# MCU.net
KiCad netlist of a schematic drawn in Altium Designer
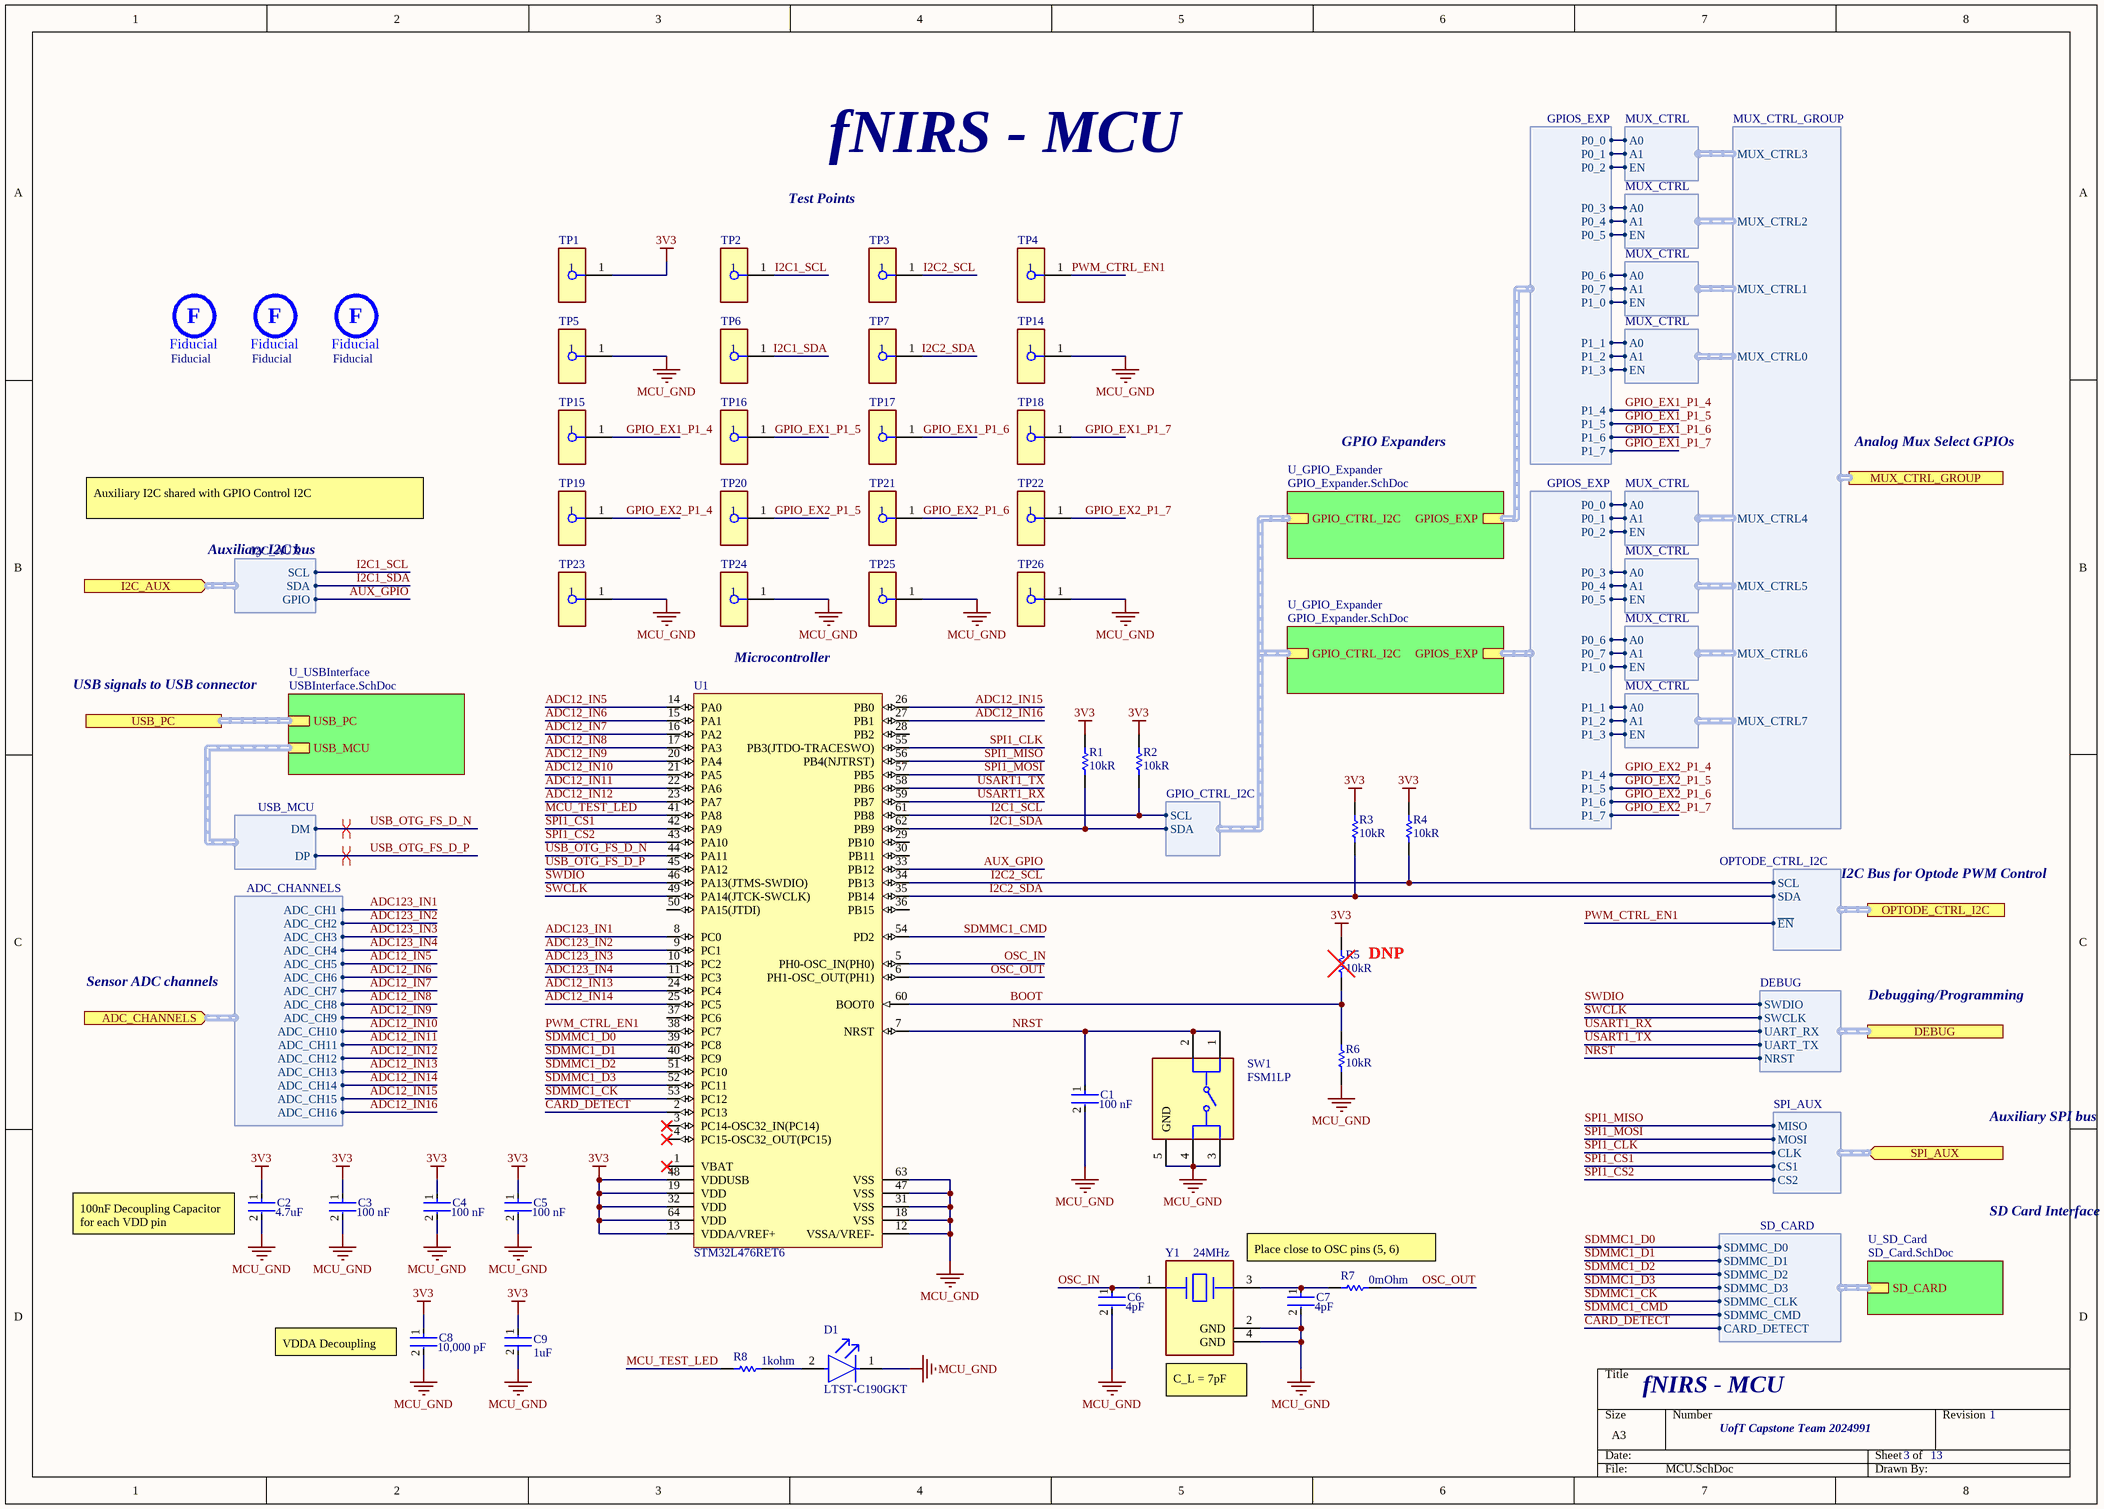
[diagram p0: MCU.SchDoc]

(export (version "E")
  (design (tool "Eeschema 10.0.6"))
  (components
    (comp (ref "C1")
      (value "CC0603KRX7R7BB104")
      (footprint "FP-CC0603-DA-MFG")
      (description "CAP CER 0.1UF 16V X7R 0603")
      (fields
        (field (name "OCTOPART") "https://octopart.com/cc0603krx7r7bb104-yageo-192941")
        (field (name "TOLERANCE") "0.1")
        (field (name "CAPACITANCE") "100 nF")
      )
      (libsource (lib "Altium Content Vault") (part "11868f565c42a9108669ba33697ecf6"))
    )
    (comp (ref "C2")
      (value "C0603C475K9PACTU")
      (footprint "FP-C0603-CG-MFG")
      (description "CAP CER 4.7UF 6.3V X5R 0603")
      (fields
        (field (name "TOLERANCE") "10%")
        (field (name "MANUFACTURER") "Kemet")
        (field (name "CAPACITANCE") "4.7uF")
      )
      (libsource (lib "Altium Content Vault") (part "11868f565c42a9108669ba33697ecf6"))
    )
    (comp (ref "C3")
      (value "CC0603KRX7R7BB104")
      (footprint "FP-CC0603-DA-MFG")
      (description "CAP CER 0.1UF 16V X7R 0603")
      (fields
        (field (name "OCTOPART") "https://octopart.com/cc0603krx7r7bb104-yageo-192941")
        (field (name "TOLERANCE") "0.1")
        (field (name "CAPACITANCE") "100 nF")
      )
      (libsource (lib "Altium Content Vault") (part "11868f565c42a9108669ba33697ecf6"))
    )
    (comp (ref "C4")
      (value "CC0603KRX7R7BB104")
      (footprint "FP-CC0603-DA-MFG")
      (description "CAP CER 0.1UF 16V X7R 0603")
      (fields
        (field (name "OCTOPART") "https://octopart.com/cc0603krx7r7bb104-yageo-192941")
        (field (name "TOLERANCE") "0.1")
        (field (name "CAPACITANCE") "100 nF")
      )
      (libsource (lib "Altium Content Vault") (part "11868f565c42a9108669ba33697ecf6"))
    )
    (comp (ref "C5")
      (value "CC0603KRX7R7BB104")
      (footprint "FP-CC0603-DA-MFG")
      (description "CAP CER 0.1UF 16V X7R 0603")
      (fields
        (field (name "OCTOPART") "https://octopart.com/cc0603krx7r7bb104-yageo-192941")
        (field (name "TOLERANCE") "0.1")
        (field (name "CAPACITANCE") "100 nF")
      )
      (libsource (lib "Altium Content Vault") (part "11868f565c42a9108669ba33697ecf6"))
    )
    (comp (ref "C6")
      (value "CL10C040CB8NNNC")
      (footprint "FP-CL10-IPC_A")
      (description "Cap Ceramic 4pF 50V C0G ±0.25pF Pad SMD 0603 +125°C T/R")
      (fields (field (name "CAPACITANCE") "4pF") (field (name "TOLERANCE") "-0.25%"))
      (libsource (lib "Altium Content Vault") (part "b4654b650e69147ec39a6b967a45e02"))
    )
    (comp (ref "C7")
      (value "CL10C040CB8NNNC")
      (footprint "FP-CL10-IPC_A")
      (description "Cap Ceramic 4pF 50V C0G ±0.25pF Pad SMD 0603 +125°C T/R")
      (fields (field (name "CAPACITANCE") "4pF") (field (name "TOLERANCE") "-0.25%"))
      (libsource (lib "Altium Content Vault") (part "b4654b650e69147ec39a6b967a45e02"))
    )
    (comp (ref "C8")
      (value "C0603C103K2RACTU")
      (footprint "FP-C0603C-CF-MFG")
      (description "CAP CER 10000PF 200V X7R 0603")
      (fields
        (field (name "MANUFACTURER") "KEMET")
        (field (name "OCTOPART") "https://octopart.com/c0603c103k2ractu-kemet-1061947")
        (field (name "CAPACITANCE") "10,000 pF")
      )
      (libsource (lib "Altium Content Vault") (part "b4654b650e69147ec39a6b967a45e02"))
    )
    (comp (ref "C9")
      (value "C1608X5R1H105K080AB")
      (footprint "FP-C1608-080-0_1-IPC_B")
      (description "Multilayer Ceramic Capacitors 1μF ±10% 50V X5R SMD 0603")
      (fields
        (field (name "VOLTAGE") "50V")
        (field (name "CAPACITANCE") "1uF")
        (field (name "TOLERANCE") "10%")
      )
      (libsource (lib "Altium Content Vault") (part "236180d848d6139a670b325ea6854c9"))
    )
    (comp (ref "D1")
      (value "LTST-C190GKT")
      (footprint "FP-LTST-C190GKT-MFG")
      (description "LED GREEN CLEAR CHIP SMD")
      (fields (field (name "VOLTAGE") "2V"))
      (libsource (lib "Altium Content Vault") (part "8706943c75ba83719d021d2fdc84c58"))
    )
    (comp (ref "Fi1")
      (value "Fiducial")
      (footprint "Fiducial-Footprint-1")
      (description "Fiducial for pick-and-place")
      (libsource (lib "Blue Sky Solar Racing") (part "Fiducial"))
    )
    (comp (ref "Fi2")
      (value "Fiducial")
      (footprint "Fiducial-Footprint-1")
      (description "Fiducial for pick-and-place")
      (libsource (lib "Blue Sky Solar Racing") (part "Fiducial"))
    )
    (comp (ref "Fi3")
      (value "Fiducial")
      (footprint "Fiducial-Footprint-1")
      (description "Fiducial for pick-and-place")
      (libsource (lib "Blue Sky Solar Racing") (part "Fiducial"))
    )
    (comp (ref "R1")
      (value "CRCW060310K0FKEA")
      (footprint "RESC1609X50X30NL8T20")
      (description "Chip Resistor, 10 KOhm, +/- 1%, 100 mW, -55 to 155 degC, 0603 (1608 Metric), RoHS, Tape and Reel")
      (fields (field (name "MANUFACTURER") "Vishay Semiconductor") (field (name "RESISTANCE") "10kR"))
      (libsource (lib "Altium Content Vault") (part "RES-2"))
    )
    (comp (ref "R2")
      (value "CRCW060310K0FKEA")
      (footprint "RESC1609X50X30NL8T20")
      (description "Chip Resistor, 10 KOhm, +/- 1%, 100 mW, -55 to 155 degC, 0603 (1608 Metric), RoHS, Tape and Reel")
      (fields (field (name "MANUFACTURER") "Vishay Semiconductor") (field (name "RESISTANCE") "10kR"))
      (libsource (lib "Altium Content Vault") (part "RES-2"))
    )
    (comp (ref "R3")
      (value "CRCW060310K0FKEA")
      (footprint "RESC1609X50X30NL8T20")
      (description "Chip Resistor, 10 KOhm, +/- 1%, 100 mW, -55 to 155 degC, 0603 (1608 Metric), RoHS, Tape and Reel")
      (fields (field (name "MANUFACTURER") "Vishay Semiconductor") (field (name "RESISTANCE") "10kR"))
      (libsource (lib "Altium Content Vault") (part "RES-2"))
    )
    (comp (ref "R4")
      (value "CRCW060310K0FKEA")
      (footprint "RESC1609X50X30NL8T20")
      (description "Chip Resistor, 10 KOhm, +/- 1%, 100 mW, -55 to 155 degC, 0603 (1608 Metric), RoHS, Tape and Reel")
      (fields (field (name "MANUFACTURER") "Vishay Semiconductor") (field (name "RESISTANCE") "10kR"))
      (libsource (lib "Altium Content Vault") (part "RES-2"))
    )
    (comp (ref "R5")
      (value "CRCW060310K0FKEA")
      (footprint "RESC1609X50X30NL8T20")
      (description "Chip Resistor, 10 KOhm, +/- 1%, 100 mW, -55 to 155 degC, 0603 (1608 Metric), RoHS, Tape and Reel")
      (fields (field (name "MANUFACTURER") "Vishay Semiconductor") (field (name "RESISTANCE") "10kR"))
      (libsource (lib "Altium Content Vault") (part "RES-2"))
    )
    (comp (ref "R6")
      (value "CRCW060310K0FKEA")
      (footprint "RESC1609X50X30NL8T20")
      (description "Chip Resistor, 10 KOhm, +/- 1%, 100 mW, -55 to 155 degC, 0603 (1608 Metric), RoHS, Tape and Reel")
      (fields (field (name "MANUFACTURER") "Vishay Semiconductor") (field (name "RESISTANCE") "10kR"))
      (libsource (lib "Altium Content Vault") (part "RES-2"))
    )
    (comp (ref "R7")
      (value "RC0603JR-070RL")
      (footprint "RESC1608X55X25ML10T15")
      (description "Chip Resistor, 0 Ohm, +/- 5%, 0.1 W, -55 to 155 degC, 0603 (1608 Metric), RoHS, Tape and Reel")
      (fields
        (field (name "TOLERANCE") "5%")
        (field (name "RESISTANCE") "0mOhm")
        (field (name "MANUFACTURER") "Yageo")
      )
      (libsource (lib "Altium Content Vault") (part "RES-2"))
    )
    (comp (ref "R8")
      (value "RC0603JR-071KL")
      (footprint "RESC1608X55X25ML10T15")
      (description "Chip Resistor, 1 KOhm, +/- 5%, 0.063 W, -55 to 155 degC, 0603 (1608 Metric), RoHS, Tape and Reel")
      (fields (field (name "RESISTANCE") "1kohm") (field (name "MANUFACTURER") "Yageo"))
      (libsource (lib "Altium Content Vault") (part "RES-2"))
    )
    (comp (ref "SW1")
      (value "FSM1LP")
      (footprint "FP-FSM1LP-MFG")
      (description "SWITCH TACTILE SPST-NO 0.05A 24V")
      (libsource (lib "Altium Content Vault") (part "3a9e64be5c1b186b34f28721102267a"))
    )
    (comp (ref "TP1")
      (value "S2761-46R")
      (footprint "FP-S2761-46R-MFG")
      (description "PC TEST POINT NATURAL")
      (libsource (lib "Altium Content Vault") (part "98815daf2f2c152b0c43f5ab9800df6"))
    )
    (comp (ref "TP2")
      (value "S2761-46R")
      (footprint "FP-S2761-46R-MFG")
      (description "PC TEST POINT NATURAL")
      (libsource (lib "Altium Content Vault") (part "98815daf2f2c152b0c43f5ab9800df6"))
    )
    (comp (ref "TP3")
      (value "S2761-46R")
      (footprint "FP-S2761-46R-MFG")
      (description "PC TEST POINT NATURAL")
      (libsource (lib "Altium Content Vault") (part "98815daf2f2c152b0c43f5ab9800df6"))
    )
    (comp (ref "TP4")
      (value "S2761-46R")
      (footprint "FP-S2761-46R-MFG")
      (description "PC TEST POINT NATURAL")
      (libsource (lib "Altium Content Vault") (part "98815daf2f2c152b0c43f5ab9800df6"))
    )
    (comp (ref "TP5")
      (value "S2761-46R")
      (footprint "FP-S2761-46R-MFG")
      (description "PC TEST POINT NATURAL")
      (libsource (lib "Altium Content Vault") (part "98815daf2f2c152b0c43f5ab9800df6"))
    )
    (comp (ref "TP6")
      (value "S2761-46R")
      (footprint "FP-S2761-46R-MFG")
      (description "PC TEST POINT NATURAL")
      (libsource (lib "Altium Content Vault") (part "98815daf2f2c152b0c43f5ab9800df6"))
    )
    (comp (ref "TP7")
      (value "S2761-46R")
      (footprint "FP-S2761-46R-MFG")
      (description "PC TEST POINT NATURAL")
      (libsource (lib "Altium Content Vault") (part "98815daf2f2c152b0c43f5ab9800df6"))
    )
    (comp (ref "TP14")
      (value "S2761-46R")
      (footprint "FP-S2761-46R-MFG")
      (description "PC TEST POINT NATURAL")
      (libsource (lib "Altium Content Vault") (part "98815daf2f2c152b0c43f5ab9800df6"))
    )
    (comp (ref "TP15")
      (value "S2761-46R")
      (footprint "FP-S2761-46R-MFG")
      (description "PC TEST POINT NATURAL")
      (libsource (lib "Altium Content Vault") (part "98815daf2f2c152b0c43f5ab9800df6"))
    )
    (comp (ref "TP16")
      (value "S2761-46R")
      (footprint "FP-S2761-46R-MFG")
      (description "PC TEST POINT NATURAL")
      (libsource (lib "Altium Content Vault") (part "98815daf2f2c152b0c43f5ab9800df6"))
    )
    (comp (ref "TP17")
      (value "S2761-46R")
      (footprint "FP-S2761-46R-MFG")
      (description "PC TEST POINT NATURAL")
      (libsource (lib "Altium Content Vault") (part "98815daf2f2c152b0c43f5ab9800df6"))
    )
    (comp (ref "TP18")
      (value "S2761-46R")
      (footprint "FP-S2761-46R-MFG")
      (description "PC TEST POINT NATURAL")
      (libsource (lib "Altium Content Vault") (part "98815daf2f2c152b0c43f5ab9800df6"))
    )
    (comp (ref "TP19")
      (value "S2761-46R")
      (footprint "FP-S2761-46R-MFG")
      (description "PC TEST POINT NATURAL")
      (libsource (lib "Altium Content Vault") (part "98815daf2f2c152b0c43f5ab9800df6"))
    )
    (comp (ref "TP20")
      (value "S2761-46R")
      (footprint "FP-S2761-46R-MFG")
      (description "PC TEST POINT NATURAL")
      (libsource (lib "Altium Content Vault") (part "98815daf2f2c152b0c43f5ab9800df6"))
    )
    (comp (ref "TP21")
      (value "S2761-46R")
      (footprint "FP-S2761-46R-MFG")
      (description "PC TEST POINT NATURAL")
      (libsource (lib "Altium Content Vault") (part "98815daf2f2c152b0c43f5ab9800df6"))
    )
    (comp (ref "TP22")
      (value "S2761-46R")
      (footprint "FP-S2761-46R-MFG")
      (description "PC TEST POINT NATURAL")
      (libsource (lib "Altium Content Vault") (part "98815daf2f2c152b0c43f5ab9800df6"))
    )
    (comp (ref "TP23")
      (value "S2761-46R")
      (footprint "FP-S2761-46R-MFG")
      (description "PC TEST POINT NATURAL")
      (libsource (lib "Altium Content Vault") (part "98815daf2f2c152b0c43f5ab9800df6"))
    )
    (comp (ref "TP24")
      (value "S2761-46R")
      (footprint "FP-S2761-46R-MFG")
      (description "PC TEST POINT NATURAL")
      (libsource (lib "Altium Content Vault") (part "98815daf2f2c152b0c43f5ab9800df6"))
    )
    (comp (ref "TP25")
      (value "S2761-46R")
      (footprint "FP-S2761-46R-MFG")
      (description "PC TEST POINT NATURAL")
      (libsource (lib "Altium Content Vault") (part "98815daf2f2c152b0c43f5ab9800df6"))
    )
    (comp (ref "TP26")
      (value "S2761-46R")
      (footprint "FP-S2761-46R-MFG")
      (description "PC TEST POINT NATURAL")
      (libsource (lib "Altium Content Vault") (part "98815daf2f2c152b0c43f5ab9800df6"))
    )
    (comp (ref "U1")
      (value "STM32L476RET6")
      (footprint "STM-LQFP64_L")
      (fields (field (name "MANUFACTURER") "STMicroelectronics"))
      (libsource (lib "Altium Content Vault") (part "MC-ARM-STM32L4X6-LQFP64"))
    )
    (comp (ref "Y1")
      (value "ABM11W-24.0000MHZ-7-B1U-T3")
      (footprint "FP-ABM11W-MFG")
      (description "Crystal 24MHz ±10ppm 7pF SMD-4 2mm x 1.6mm")
      (fields (field (name "FREQUENCY") "24MHz"))
      (libsource (lib "Altium Content Vault") (part "5fba445d8d5f95165d6b3865099b029"))
    )
  )
  (nets
    (net (code "13") (name "/ADC12_IN5") (class "Default")
      (node (ref "U1") (pin "14") (pinfunction "PA0_14") (pintype "bidirectional"))
    )
    (net (code "14") (name "/ADC12_IN6") (class "Default")
      (node (ref "U1") (pin "15") (pinfunction "PA1_15") (pintype "bidirectional"))
    )
    (net (code "15") (name "/ADC12_IN7") (class "Default")
      (node (ref "U1") (pin "16") (pinfunction "PA2_16") (pintype "bidirectional"))
    )
    (net (code "16") (name "/ADC12_IN8") (class "Default")
      (node (ref "U1") (pin "17") (pinfunction "PA3_17") (pintype "bidirectional"))
    )
    (net (code "17") (name "/ADC12_IN9") (class "Default")
      (node (ref "U1") (pin "20") (pinfunction "PA4_20") (pintype "bidirectional"))
    )
    (net (code "18") (name "/ADC12_IN10") (class "Default")
      (node (ref "U1") (pin "21") (pinfunction "PA5_21") (pintype "bidirectional"))
    )
    (net (code "19") (name "/ADC12_IN11") (class "Default")
      (node (ref "U1") (pin "22") (pinfunction "PA6_22") (pintype "bidirectional"))
    )
    (net (code "20") (name "/ADC12_IN12") (class "Default")
      (node (ref "U1") (pin "23") (pinfunction "PA7_23") (pintype "bidirectional"))
    )
    (net (code "21") (name "/ADC12_IN13") (class "Default")
      (node (ref "U1") (pin "24") (pinfunction "PC4_24") (pintype "bidirectional"))
    )
    (net (code "22") (name "/ADC12_IN14") (class "Default")
      (node (ref "U1") (pin "25") (pinfunction "PC5_25") (pintype "bidirectional"))
    )
    (net (code "23") (name "/ADC12_IN15") (class "Default")
      (node (ref "U1") (pin "26") (pinfunction "PB0_26") (pintype "bidirectional"))
    )
    (net (code "24") (name "/ADC12_IN16") (class "Default")
      (node (ref "U1") (pin "27") (pinfunction "PB1_27") (pintype "bidirectional"))
    )
    (net (code "25") (name "/ADC123_IN1") (class "Default")
      (node (ref "U1") (pin "8") (pinfunction "PC0_8") (pintype "bidirectional"))
    )
    (net (code "26") (name "/ADC123_IN2") (class "Default")
      (node (ref "U1") (pin "9") (pinfunction "PC1_9") (pintype "bidirectional"))
    )
    (net (code "27") (name "/ADC123_IN3") (class "Default")
      (node (ref "U1") (pin "10") (pinfunction "PC2_10") (pintype "bidirectional"))
    )
    (net (code "28") (name "/ADC123_IN4") (class "Default")
      (node (ref "U1") (pin "11") (pinfunction "PC3_11") (pintype "bidirectional"))
    )
    (net (code "29") (name "/AUX_GPIO") (class "Default")
      (node (ref "U1") (pin "33") (pinfunction "PB12_33") (pintype "bidirectional"))
    )
    (net (code "30") (name "/BOOT") (class "Default")
      (node (ref "R5") (pin "1") (pinfunction "1_1") (pintype "passive"))
      (node (ref "R6") (pin "2") (pinfunction "2_2") (pintype "passive"))
      (node (ref "U1") (pin "60") (pinfunction "BOOT0_60") (pintype "input"))
    )
    (net (code "31") (name "/CARD_DETECT") (class "Default")
      (node (ref "U1") (pin "2") (pinfunction "PC13_2") (pintype "bidirectional"))
    )
    (net (code "32") (name "/GPIO_EX1_P1_4") (class "Default")
      (node (ref "TP15") (pin "1") (pinfunction "1_1") (pintype "passive"))
    )
    (net (code "33") (name "/GPIO_EX1_P1_5") (class "Default")
      (node (ref "TP16") (pin "1") (pinfunction "1_1") (pintype "passive"))
    )
    (net (code "34") (name "/GPIO_EX1_P1_6") (class "Default")
      (node (ref "TP17") (pin "1") (pinfunction "1_1") (pintype "passive"))
    )
    (net (code "35") (name "/GPIO_EX1_P1_7") (class "Default")
      (node (ref "TP18") (pin "1") (pinfunction "1_1") (pintype "passive"))
    )
    (net (code "36") (name "/GPIO_EX2_P1_4") (class "Default")
      (node (ref "TP19") (pin "1") (pinfunction "1_1") (pintype "passive"))
    )
    (net (code "37") (name "/GPIO_EX2_P1_5") (class "Default")
      (node (ref "TP20") (pin "1") (pinfunction "1_1") (pintype "passive"))
    )
    (net (code "38") (name "/GPIO_EX2_P1_6") (class "Default")
      (node (ref "TP21") (pin "1") (pinfunction "1_1") (pintype "passive"))
    )
    (net (code "39") (name "/GPIO_EX2_P1_7") (class "Default")
      (node (ref "TP22") (pin "1") (pinfunction "1_1") (pintype "passive"))
    )
    (net (code "40") (name "/I2C1_SCL") (class "Default")
      (node (ref "R2") (pin "1") (pinfunction "1_1") (pintype "passive"))
      (node (ref "TP2") (pin "1") (pinfunction "1_1") (pintype "passive"))
      (node (ref "U1") (pin "61") (pinfunction "PB8_61") (pintype "bidirectional"))
    )
    (net (code "41") (name "/I2C1_SDA") (class "Default")
      (node (ref "R1") (pin "1") (pinfunction "1_1") (pintype "passive"))
      (node (ref "TP6") (pin "1") (pinfunction "1_1") (pintype "passive"))
      (node (ref "U1") (pin "62") (pinfunction "PB9_62") (pintype "bidirectional"))
    )
    (net (code "42") (name "/I2C2_SCL") (class "Default")
      (node (ref "R4") (pin "1") (pinfunction "1_1") (pintype "passive"))
      (node (ref "TP3") (pin "1") (pinfunction "1_1") (pintype "passive"))
      (node (ref "U1") (pin "34") (pinfunction "PB13_34") (pintype "bidirectional"))
    )
    (net (code "43") (name "/I2C2_SDA") (class "Default")
      (node (ref "R3") (pin "1") (pinfunction "1_1") (pintype "passive"))
      (node (ref "TP7") (pin "1") (pinfunction "1_1") (pintype "passive"))
      (node (ref "U1") (pin "35") (pinfunction "PB14_35") (pintype "bidirectional"))
    )
    (net (code "44") (name "/MCU_TEST_LED") (class "Default")
      (node (ref "R8") (pin "1") (pinfunction "1_1") (pintype "passive"))
      (node (ref "U1") (pin "41") (pinfunction "PA8_41") (pintype "bidirectional"))
    )
    (net (code "46") (name "/NRST") (class "Default")
      (node (ref "C1") (pin "1") (pinfunction "1_1") (pintype "passive"))
      (node (ref "SW1") (pin "1") (pinfunction "1_1") (pintype "passive"))
      (node (ref "SW1") (pin "2") (pinfunction "2_2") (pintype "passive"))
      (node (ref "U1") (pin "7") (pinfunction "NRST_7") (pintype "bidirectional"))
    )
    (net (code "47") (name "/OSC_IN") (class "Default")
      (node (ref "C6") (pin "1") (pinfunction "1_1") (pintype "passive"))
      (node (ref "U1") (pin "5") (pinfunction "PH0-OSC_IN(PH0)_5") (pintype "bidirectional"))
      (node (ref "Y1") (pin "1") (pinfunction "1_1") (pintype "passive"))
    )
    (net (code "48") (name "/OSC_OUT") (class "Default")
      (node (ref "R7") (pin "2") (pinfunction "2_2") (pintype "passive"))
      (node (ref "U1") (pin "6") (pinfunction "PH1-OSC_OUT(PH1)_6") (pintype "bidirectional"))
    )
    (net (code "49") (name "/PWM_CTRL_EN1") (class "Default")
      (node (ref "TP4") (pin "1") (pinfunction "1_1") (pintype "passive"))
      (node (ref "U1") (pin "38") (pinfunction "PC7_38") (pintype "bidirectional"))
    )
    (net (code "50") (name "/SDMMC1_CK") (class "Default")
      (node (ref "U1") (pin "53") (pinfunction "PC12_53") (pintype "bidirectional"))
    )
    (net (code "51") (name "/SDMMC1_CMD") (class "Default")
      (node (ref "U1") (pin "54") (pinfunction "PD2_54") (pintype "bidirectional"))
    )
    (net (code "52") (name "/SDMMC1_D0") (class "Default")
      (node (ref "U1") (pin "39") (pinfunction "PC8_39") (pintype "bidirectional"))
    )
    (net (code "53") (name "/SDMMC1_D1") (class "Default")
      (node (ref "U1") (pin "40") (pinfunction "PC9_40") (pintype "bidirectional"))
    )
    (net (code "54") (name "/SDMMC1_D2") (class "Default")
      (node (ref "U1") (pin "51") (pinfunction "PC10_51") (pintype "bidirectional"))
    )
    (net (code "55") (name "/SDMMC1_D3") (class "Default")
      (node (ref "U1") (pin "52") (pinfunction "PC11_52") (pintype "bidirectional"))
    )
    (net (code "56") (name "/SPI1_CLK") (class "Default")
      (node (ref "U1") (pin "55") (pinfunction "PB3(JTDO-TRACESWO)_55") (pintype "bidirectional"))
    )
    (net (code "57") (name "/SPI1_CS1") (class "Default")
      (node (ref "U1") (pin "42") (pinfunction "PA9_42") (pintype "bidirectional"))
    )
    (net (code "58") (name "/SPI1_CS2") (class "Default")
      (node (ref "U1") (pin "43") (pinfunction "PA10_43") (pintype "bidirectional"))
    )
    (net (code "59") (name "/SPI1_MISO") (class "Default")
      (node (ref "U1") (pin "56") (pinfunction "PB4(NJTRST)_56") (pintype "bidirectional"))
    )
    (net (code "60") (name "/SPI1_MOSI") (class "Default")
      (node (ref "U1") (pin "57") (pinfunction "PB5_57") (pintype "bidirectional"))
    )
    (net (code "61") (name "/SWCLK") (class "Default")
      (node (ref "U1") (pin "49") (pinfunction "PA14(JTCK-SWCLK)_49") (pintype "bidirectional"))
    )
    (net (code "62") (name "/SWDIO") (class "Default")
      (node (ref "U1") (pin "46") (pinfunction "PA13(JTMS-SWDIO)_46") (pintype "bidirectional"))
    )
    (net (code "63") (name "/USART1_RX") (class "Default")
      (node (ref "U1") (pin "59") (pinfunction "PB7_59") (pintype "bidirectional"))
    )
    (net (code "64") (name "/USART1_TX") (class "Default")
      (node (ref "U1") (pin "58") (pinfunction "PB6_58") (pintype "bidirectional"))
    )
    (net (code "65") (name "/USB_OTG_FS_D_N") (class "Default")
      (node (ref "U1") (pin "44") (pinfunction "PA11_44") (pintype "bidirectional"))
    )
    (net (code "66") (name "/USB_OTG_FS_D_P") (class "Default")
      (node (ref "U1") (pin "45") (pinfunction "PA12_45") (pintype "bidirectional"))
    )
    (net (code "78") (name "3V3") (class "Default")
      (node (ref "C2") (pin "1") (pinfunction "1_1") (pintype "passive"))
      (node (ref "C3") (pin "1") (pinfunction "1_1") (pintype "passive"))
      (node (ref "C4") (pin "1") (pinfunction "1_1") (pintype "passive"))
      (node (ref "C5") (pin "1") (pinfunction "1_1") (pintype "passive"))
      (node (ref "C8") (pin "1") (pinfunction "1_1") (pintype "passive"))
      (node (ref "C9") (pin "1") (pinfunction "1_1") (pintype "passive"))
      (node (ref "R1") (pin "2") (pinfunction "2_2") (pintype "passive"))
      (node (ref "R2") (pin "2") (pinfunction "2_2") (pintype "passive"))
      (node (ref "R3") (pin "2") (pinfunction "2_2") (pintype "passive"))
      (node (ref "R4") (pin "2") (pinfunction "2_2") (pintype "passive"))
      (node (ref "R5") (pin "2") (pinfunction "2_2") (pintype "passive"))
      (node (ref "TP1") (pin "1") (pinfunction "1_1") (pintype "passive"))
      (node (ref "U1") (pin "13") (pinfunction "VDDA/VREF+_13") (pintype "power_in"))
      (node (ref "U1") (pin "19") (pinfunction "VDD_19") (pintype "power_in"))
      (node (ref "U1") (pin "32") (pinfunction "VDD_32") (pintype "power_in"))
      (node (ref "U1") (pin "48") (pinfunction "VDDUSB_48") (pintype "power_in"))
      (node (ref "U1") (pin "64") (pinfunction "VDD_64") (pintype "power_in"))
    )
    (net (code "79") (name "MCU_GND") (class "Default")
      (node (ref "C1") (pin "2") (pinfunction "2_2") (pintype "passive"))
      (node (ref "C2") (pin "2") (pinfunction "2_2") (pintype "passive"))
      (node (ref "C3") (pin "2") (pinfunction "2_2") (pintype "passive"))
      (node (ref "C4") (pin "2") (pinfunction "2_2") (pintype "passive"))
      (node (ref "C5") (pin "2") (pinfunction "2_2") (pintype "passive"))
      (node (ref "C6") (pin "2") (pinfunction "2_2") (pintype "passive"))
      (node (ref "C7") (pin "2") (pinfunction "2_2") (pintype "passive"))
      (node (ref "C8") (pin "2") (pinfunction "2_2") (pintype "passive"))
      (node (ref "C9") (pin "2") (pinfunction "2_2") (pintype "passive"))
      (node (ref "D1") (pin "1") (pinfunction "C_1") (pintype "passive"))
      (node (ref "R6") (pin "1") (pinfunction "1_1") (pintype "passive"))
      (node (ref "SW1") (pin "3") (pinfunction "3_3") (pintype "passive"))
      (node (ref "SW1") (pin "4") (pinfunction "4_4") (pintype "passive"))
      (node (ref "SW1") (pin "5") (pinfunction "GND_5") (pintype "power_in"))
      (node (ref "TP14") (pin "1") (pinfunction "1_1") (pintype "passive"))
      (node (ref "TP23") (pin "1") (pinfunction "1_1") (pintype "passive"))
      (node (ref "TP24") (pin "1") (pinfunction "1_1") (pintype "passive"))
      (node (ref "TP25") (pin "1") (pinfunction "1_1") (pintype "passive"))
      (node (ref "TP26") (pin "1") (pinfunction "1_1") (pintype "passive"))
      (node (ref "TP5") (pin "1") (pinfunction "1_1") (pintype "passive"))
      (node (ref "U1") (pin "12") (pinfunction "VSSA/VREF-_12") (pintype "power_in"))
      (node (ref "U1") (pin "18") (pinfunction "VSS_18") (pintype "power_in"))
      (node (ref "U1") (pin "31") (pinfunction "VSS_31") (pintype "power_in"))
      (node (ref "U1") (pin "47") (pinfunction "VSS_47") (pintype "power_in"))
      (node (ref "U1") (pin "63") (pinfunction "VSS_63") (pintype "power_in"))
      (node (ref "Y1") (pin "2") (pinfunction "GND_2") (pintype "power_in"))
      (node (ref "Y1") (pin "4") (pinfunction "GND_4") (pintype "power_in"))
    )
    (net (code "80") (name "Net-(C7-Pad1)") (class "Default")
      (node (ref "C7") (pin "1") (pinfunction "1_1") (pintype "passive"))
      (node (ref "R7") (pin "1") (pinfunction "1_1") (pintype "passive"))
      (node (ref "Y1") (pin "3") (pinfunction "3_3") (pintype "passive"))
    )
    (net (code "81") (name "Net-(D1-A)") (class "Default")
      (node (ref "D1") (pin "2") (pinfunction "A_2") (pintype "passive"))
      (node (ref "R8") (pin "2") (pinfunction "2_2") (pintype "passive"))
    )
    (net (code "82") (name "unconnected-(U1-PA15(JTDI)-Pad50)") (class "Default")
      (node (ref "U1") (pin "50") (pinfunction "PA15(JTDI)_50") (pintype "bidirectional"))
    )
    (net (code "83") (name "unconnected-(U1-PB2-Pad28)") (class "Default")
      (node (ref "U1") (pin "28") (pinfunction "PB2_28") (pintype "bidirectional"))
    )
    (net (code "84") (name "unconnected-(U1-PB10-Pad29)") (class "Default")
      (node (ref "U1") (pin "29") (pinfunction "PB10_29") (pintype "bidirectional"))
    )
    (net (code "85") (name "unconnected-(U1-PB11-Pad30)") (class "Default")
      (node (ref "U1") (pin "30") (pinfunction "PB11_30") (pintype "bidirectional"))
    )
    (net (code "86") (name "unconnected-(U1-PB15-Pad36)") (class "Default")
      (node (ref "U1") (pin "36") (pinfunction "PB15_36") (pintype "bidirectional"))
    )
    (net (code "87") (name "unconnected-(U1-PC6-Pad37)") (class "Default")
      (node (ref "U1") (pin "37") (pinfunction "PC6_37") (pintype "bidirectional"))
    )
    (net (code "88") (name "unconnected-(U1-PC14-OSC32_IN(PC14)-Pad3)") (class "Default")
      (node (ref "U1") (pin "3") (pinfunction "PC14-OSC32_IN(PC14)_3") (pintype "bidirectional+no_connect"))
    )
    (net (code "89") (name "unconnected-(U1-PC15-OSC32_OUT(PC15)-Pad4)") (class "Default")
      (node (ref "U1") (pin "4") (pinfunction "PC15-OSC32_OUT(PC15)_4") (pintype "bidirectional+no_connect"))
    )
    (net (code "90") (name "unconnected-(U1-VBAT-Pad1)") (class "Default")
      (node (ref "U1") (pin "1") (pinfunction "VBAT_1") (pintype "power_in+no_connect"))
    )
  )
)
